# NOT-B.net
KiCad netlist of a schematic drawn in EAGLE
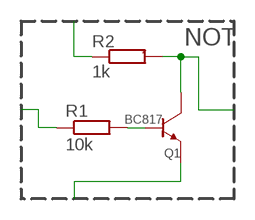
[diagram p0: schematic, sheet 1]

(export (version "E")
  (design (tool "Eeschema 10.0.6"))
  (components
    (comp (ref "Q1")
      (value "BC817")
      (footprint "eagle-import:SOT23")
      (libsource (lib "eagle-import") (part "TRANSISTOR-NPN-GENERIC-SOT23-BECDEFAULT"))
    )
    (comp (ref "R1")
      (value "10k")
      (footprint "eagle-import:R0603")
      (libsource (lib "eagle-import") (part "R-EU_R0603"))
    )
    (comp (ref "R2")
      (value "1k")
      (footprint "eagle-import:R0603-MARK")
      (libsource (lib "eagle-import") (part "R-EU-MARKEDR0603"))
    )
  )
  (nets
    (net (code "1") (name "Net-(Q1-BASE)") (class "Default")
      (node (ref "Q1") (pin "P$1") (pinfunction "BASE_P$1") (pintype "bidirectional"))
      (node (ref "R1") (pin "2") (pinfunction "2_2") (pintype "passive"))
    )
    (net (code "2") (name "Net-(Q1-COLLECTOR)") (class "Default")
      (node (ref "Q1") (pin "P$3") (pinfunction "COLLECTOR_P$3") (pintype "bidirectional"))
      (node (ref "R2") (pin "2") (pinfunction "2_2") (pintype "passive"))
    )
    (net (code "3") (name "unconnected-(Q1-EMITTER-PadP$2)") (class "Default")
      (node (ref "Q1") (pin "P$2") (pinfunction "EMITTER_P$2") (pintype "bidirectional"))
    )
    (net (code "4") (name "unconnected-(R1-Pad1)") (class "Default")
      (node (ref "R1") (pin "1") (pinfunction "1_1") (pintype "passive"))
    )
    (net (code "5") (name "unconnected-(R2-Pad1)") (class "Default")
      (node (ref "R2") (pin "1") (pinfunction "1_1") (pintype "passive"))
    )
  )
)
